# pcb.net
KiCad netlist of a schematic drawn in EAGLE
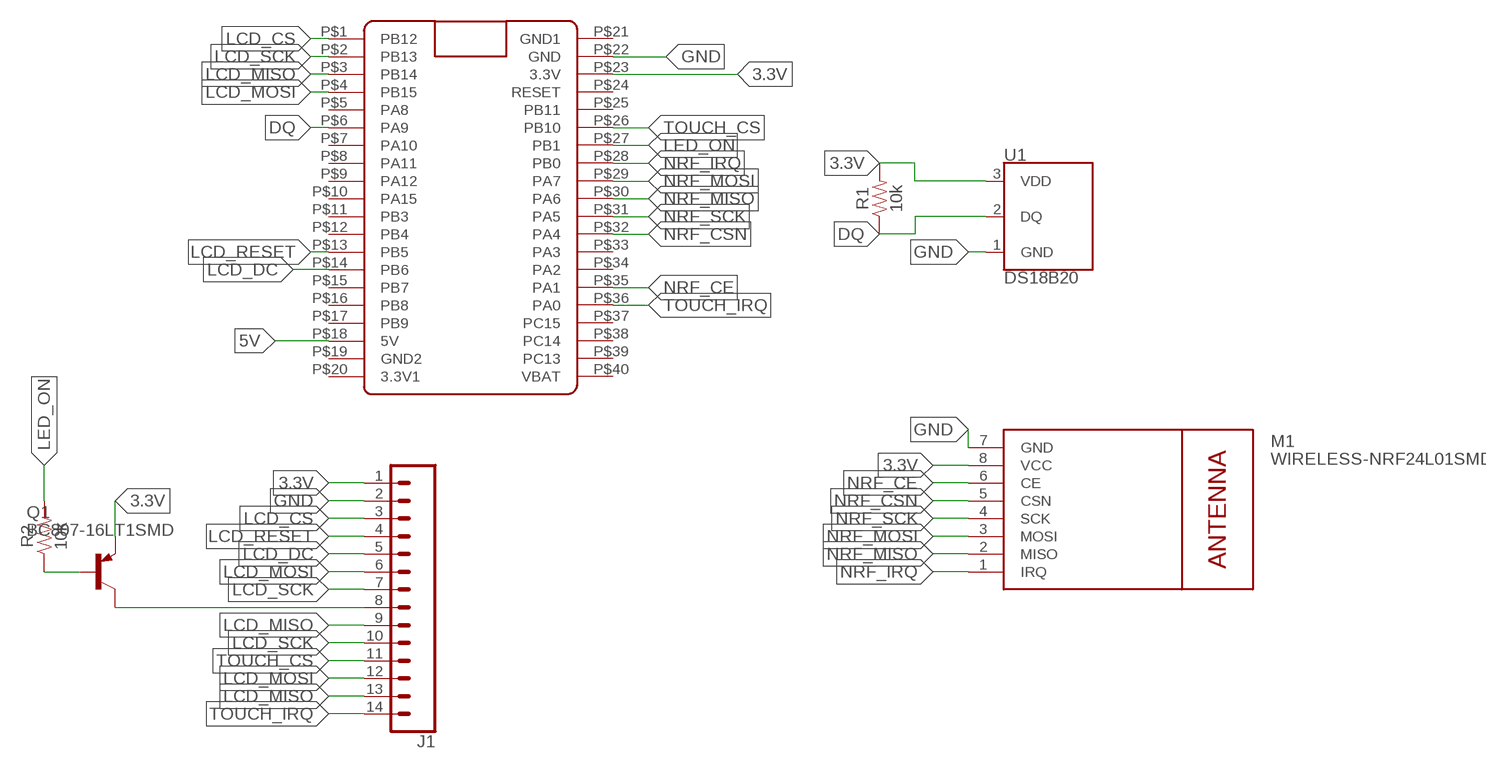
[diagram p0: schematic, sheet 1]

(export (version "E")
  (design (tool "Eeschema 10.0.6"))
  (components
    (comp (ref "J1")
      (value "CONN_14")
      (footprint "eagle-import:1X14")
      (libsource (lib "eagle-import") (part "CONN_14"))
    )
    (comp (ref "M1")
      (value "WIRELESS-NRF24L01SMD")
      (footprint "eagle-import:WIRELESS-NRF24L01-SMD")
      (libsource (lib "eagle-import") (part "WIRELESS-NRF24L01SMD"))
    )
    (comp (ref "Q1")
      (value "BC807-16LT1SMD")
      (footprint "eagle-import:SOT23-BEC")
      (libsource (lib "eagle-import") (part "BC807SMD-16LT1"))
    )
    (comp (ref "R1")
      (value "10k")
      (footprint "eagle-import:0603")
      (libsource (lib "eagle-import") (part "10KOHM-0603-1/10W-1%"))
    )
    (comp (ref "R2")
      (value "10k")
      (footprint "eagle-import:0603")
      (libsource (lib "eagle-import") (part "10KOHM-0603-1/10W-1%"))
    )
    (comp (ref "U$1")
      (value "BLUE_PILL")
      (footprint "eagle-import:BLUE_PILL")
      (libsource (lib "eagle-import") (part "BLUE_PILL"))
    )
    (comp (ref "U1")
      (value "DS18B20")
      (footprint "eagle-import:TO-92-AMMO")
      (fields (field (name "MF") "Maxim Integrated"))
      (libsource (lib "eagle-import") (part "DS18B20"))
    )
  )
  (nets
    (net (code "1") (name "/GND1") (class "Default")
      (node (ref "U$1") (pin "P$21") (pinfunction "GND1_P$21") (pintype "power_in"))
    )
    (net (code "2") (name "3.3V") (class "Default")
      (node (ref "J1") (pin "1") (pinfunction "1_1") (pintype "passive"))
      (node (ref "M1") (pin "8") (pinfunction "VCC_8") (pintype "power_in"))
      (node (ref "Q1") (pin "E") (pinfunction "E_E") (pintype "passive"))
      (node (ref "R1") (pin "2") (pinfunction "2_2") (pintype "passive"))
      (node (ref "U$1") (pin "P$23") (pinfunction "3.3V_P$23") (pintype "bidirectional"))
      (node (ref "U1") (pin "3") (pinfunction "VDD_3") (pintype "power_in"))
    )
    (net (code "3") (name "5V") (class "Default")
      (node (ref "U$1") (pin "P$18") (pinfunction "5V_P$18") (pintype "bidirectional"))
    )
    (net (code "4") (name "DQ") (class "Default")
      (node (ref "R1") (pin "1") (pinfunction "1_1") (pintype "passive"))
      (node (ref "U$1") (pin "P$6") (pinfunction "PA9_P$6") (pintype "bidirectional"))
      (node (ref "U1") (pin "2") (pinfunction "DQ_2") (pintype "bidirectional"))
    )
    (net (code "5") (name "GND") (class "Default")
      (node (ref "J1") (pin "2") (pinfunction "2_2") (pintype "passive"))
      (node (ref "M1") (pin "7") (pinfunction "GND_7") (pintype "power_in"))
      (node (ref "U$1") (pin "P$22") (pinfunction "GND_P$22") (pintype "bidirectional"))
      (node (ref "U1") (pin "1") (pinfunction "GND_1") (pintype "power_in"))
    )
    (net (code "6") (name "LCD_CS") (class "Default")
      (node (ref "J1") (pin "3") (pinfunction "3_3") (pintype "passive"))
      (node (ref "U$1") (pin "P$1") (pinfunction "PB12_P$1") (pintype "bidirectional"))
    )
    (net (code "7") (name "LCD_DC") (class "Default")
      (node (ref "J1") (pin "5") (pinfunction "5_5") (pintype "passive"))
      (node (ref "U$1") (pin "P$14") (pinfunction "PB6_P$14") (pintype "bidirectional"))
    )
    (net (code "8") (name "LCD_MISO") (class "Default")
      (node (ref "J1") (pin "13") (pinfunction "13_13") (pintype "passive"))
      (node (ref "J1") (pin "9") (pinfunction "9_9") (pintype "passive"))
      (node (ref "U$1") (pin "P$3") (pinfunction "PB14_P$3") (pintype "bidirectional"))
    )
    (net (code "9") (name "LCD_MOSI") (class "Default")
      (node (ref "J1") (pin "12") (pinfunction "12_12") (pintype "passive"))
      (node (ref "J1") (pin "6") (pinfunction "6_6") (pintype "passive"))
      (node (ref "U$1") (pin "P$4") (pinfunction "PB15_P$4") (pintype "bidirectional"))
    )
    (net (code "10") (name "LCD_RESET") (class "Default")
      (node (ref "J1") (pin "4") (pinfunction "4_4") (pintype "passive"))
      (node (ref "U$1") (pin "P$13") (pinfunction "PB5_P$13") (pintype "bidirectional"))
    )
    (net (code "11") (name "LCD_SCK") (class "Default")
      (node (ref "J1") (pin "10") (pinfunction "10_10") (pintype "passive"))
      (node (ref "J1") (pin "7") (pinfunction "7_7") (pintype "passive"))
      (node (ref "U$1") (pin "P$2") (pinfunction "PB13_P$2") (pintype "bidirectional"))
    )
    (net (code "12") (name "LED_ON") (class "Default")
      (node (ref "R2") (pin "2") (pinfunction "2_2") (pintype "passive"))
      (node (ref "U$1") (pin "P$27") (pinfunction "PB1_P$27") (pintype "bidirectional"))
    )
    (net (code "13") (name "NRF_CE") (class "Default")
      (node (ref "M1") (pin "6") (pinfunction "CE_6") (pintype "bidirectional"))
      (node (ref "U$1") (pin "P$35") (pinfunction "PA1_P$35") (pintype "bidirectional"))
    )
    (net (code "14") (name "NRF_CSN") (class "Default")
      (node (ref "M1") (pin "5") (pinfunction "CSN_5") (pintype "bidirectional"))
      (node (ref "U$1") (pin "P$32") (pinfunction "PA4_P$32") (pintype "bidirectional"))
    )
    (net (code "15") (name "NRF_IRQ") (class "Default")
      (node (ref "M1") (pin "1") (pinfunction "IRQ_1") (pintype "bidirectional"))
      (node (ref "U$1") (pin "P$28") (pinfunction "PB0_P$28") (pintype "bidirectional"))
    )
    (net (code "16") (name "NRF_MISO") (class "Default")
      (node (ref "M1") (pin "2") (pinfunction "MISO_2") (pintype "bidirectional"))
      (node (ref "U$1") (pin "P$30") (pinfunction "PA6_P$30") (pintype "bidirectional"))
    )
    (net (code "17") (name "NRF_MOSI") (class "Default")
      (node (ref "M1") (pin "3") (pinfunction "MOSI_3") (pintype "bidirectional"))
      (node (ref "U$1") (pin "P$29") (pinfunction "PA7_P$29") (pintype "bidirectional"))
    )
    (net (code "18") (name "NRF_SCK") (class "Default")
      (node (ref "M1") (pin "4") (pinfunction "SCK_4") (pintype "bidirectional"))
      (node (ref "U$1") (pin "P$31") (pinfunction "PA5_P$31") (pintype "bidirectional"))
    )
    (net (code "19") (name "Net-(J1-Pad8)") (class "Default")
      (node (ref "J1") (pin "8") (pinfunction "8_8") (pintype "passive"))
      (node (ref "Q1") (pin "C") (pinfunction "C_C") (pintype "passive"))
    )
    (net (code "20") (name "Net-(Q1-PadB)") (class "Default")
      (node (ref "Q1") (pin "B") (pinfunction "B_B") (pintype "passive"))
      (node (ref "R2") (pin "1") (pinfunction "1_1") (pintype "passive"))
    )
    (net (code "21") (name "TOUCH_CS") (class "Default")
      (node (ref "J1") (pin "11") (pinfunction "11_11") (pintype "passive"))
      (node (ref "U$1") (pin "P$26") (pinfunction "PB10_P$26") (pintype "bidirectional"))
    )
    (net (code "22") (name "TOUCH_IRQ") (class "Default")
      (node (ref "J1") (pin "14") (pinfunction "14_14") (pintype "passive"))
      (node (ref "U$1") (pin "P$36") (pinfunction "PA0_P$36") (pintype "bidirectional"))
    )
    (net (code "23") (name "unconnected-(U$1-3.3V1-PadP$20)") (class "Default")
      (node (ref "U$1") (pin "P$20") (pinfunction "3.3V1_P$20") (pintype "bidirectional"))
    )
    (net (code "24") (name "unconnected-(U$1-GND2-PadP$19)") (class "Default")
      (node (ref "U$1") (pin "P$19") (pinfunction "GND2_P$19") (pintype "bidirectional"))
    )
    (net (code "25") (name "unconnected-(U$1-PA2-PadP$34)") (class "Default")
      (node (ref "U$1") (pin "P$34") (pinfunction "PA2_P$34") (pintype "bidirectional"))
    )
    (net (code "26") (name "unconnected-(U$1-PA3-PadP$33)") (class "Default")
      (node (ref "U$1") (pin "P$33") (pinfunction "PA3_P$33") (pintype "bidirectional"))
    )
    (net (code "27") (name "unconnected-(U$1-PA8-PadP$5)") (class "Default")
      (node (ref "U$1") (pin "P$5") (pinfunction "PA8_P$5") (pintype "bidirectional"))
    )
    (net (code "28") (name "unconnected-(U$1-PA10-PadP$7)") (class "Default")
      (node (ref "U$1") (pin "P$7") (pinfunction "PA10_P$7") (pintype "bidirectional"))
    )
    (net (code "29") (name "unconnected-(U$1-PA11-PadP$8)") (class "Default")
      (node (ref "U$1") (pin "P$8") (pinfunction "PA11_P$8") (pintype "bidirectional"))
    )
    (net (code "30") (name "unconnected-(U$1-PA12-PadP$9)") (class "Default")
      (node (ref "U$1") (pin "P$9") (pinfunction "PA12_P$9") (pintype "bidirectional"))
    )
    (net (code "31") (name "unconnected-(U$1-PA15-PadP$10)") (class "Default")
      (node (ref "U$1") (pin "P$10") (pinfunction "PA15_P$10") (pintype "bidirectional"))
    )
    (net (code "32") (name "unconnected-(U$1-PB3-PadP$11)") (class "Default")
      (node (ref "U$1") (pin "P$11") (pinfunction "PB3_P$11") (pintype "bidirectional"))
    )
    (net (code "33") (name "unconnected-(U$1-PB4-PadP$12)") (class "Default")
      (node (ref "U$1") (pin "P$12") (pinfunction "PB4_P$12") (pintype "bidirectional"))
    )
    (net (code "34") (name "unconnected-(U$1-PB7-PadP$15)") (class "Default")
      (node (ref "U$1") (pin "P$15") (pinfunction "PB7_P$15") (pintype "bidirectional"))
    )
    (net (code "35") (name "unconnected-(U$1-PB8-PadP$16)") (class "Default")
      (node (ref "U$1") (pin "P$16") (pinfunction "PB8_P$16") (pintype "bidirectional"))
    )
    (net (code "36") (name "unconnected-(U$1-PB9-PadP$17)") (class "Default")
      (node (ref "U$1") (pin "P$17") (pinfunction "PB9_P$17") (pintype "bidirectional"))
    )
    (net (code "37") (name "unconnected-(U$1-PB11-PadP$25)") (class "Default")
      (node (ref "U$1") (pin "P$25") (pinfunction "PB11_P$25") (pintype "bidirectional"))
    )
    (net (code "38") (name "unconnected-(U$1-PC13-PadP$39)") (class "Default")
      (node (ref "U$1") (pin "P$39") (pinfunction "PC13_P$39") (pintype "bidirectional"))
    )
    (net (code "39") (name "unconnected-(U$1-PC14-PadP$38)") (class "Default")
      (node (ref "U$1") (pin "P$38") (pinfunction "PC14_P$38") (pintype "bidirectional"))
    )
    (net (code "40") (name "unconnected-(U$1-PC15-PadP$37)") (class "Default")
      (node (ref "U$1") (pin "P$37") (pinfunction "PC15_P$37") (pintype "bidirectional"))
    )
    (net (code "41") (name "unconnected-(U$1-RESET-PadP$24)") (class "Default")
      (node (ref "U$1") (pin "P$24") (pinfunction "RESET_P$24") (pintype "bidirectional"))
    )
    (net (code "42") (name "unconnected-(U$1-VBAT-PadP$40)") (class "Default")
      (node (ref "U$1") (pin "P$40") (pinfunction "VBAT_P$40") (pintype "bidirectional"))
    )
  )
)
